# connector_hub.net
KiCad netlist of a schematic drawn in EAGLE
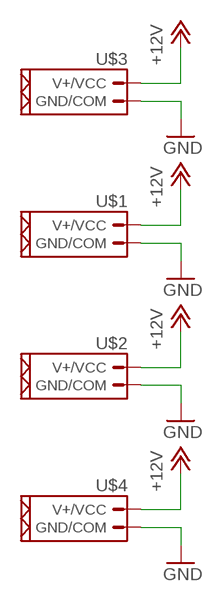
[diagram p0: schematic, sheet 1]

(export (version "E")
  (design (tool "Eeschema 10.0.6"))
  (components
    (comp (ref "U$1")
      (value "CONN_02_PUIXT60")
      (footprint "eagle-import:XT60")
      (libsource (lib "eagle-import") (part "CONN_02_PUIXT60"))
    )
    (comp (ref "U$2")
      (value "CONN_02_PUIXT60")
      (footprint "eagle-import:XT60")
      (libsource (lib "eagle-import") (part "CONN_02_PUIXT60"))
    )
    (comp (ref "U$3")
      (value "CONN_02_PUIXT60")
      (footprint "eagle-import:XT60")
      (libsource (lib "eagle-import") (part "CONN_02_PUIXT60"))
    )
    (comp (ref "U$4")
      (value "CONN_02_PUIXT60")
      (footprint "eagle-import:XT60")
      (libsource (lib "eagle-import") (part "CONN_02_PUIXT60"))
    )
  )
  (nets
    (net (code "1") (name "+12V") (class "Default")
      (node (ref "U$1") (pin "P$1") (pinfunction "V+/VCC_P$1") (pintype "passive"))
      (node (ref "U$2") (pin "P$1") (pinfunction "V+/VCC_P$1") (pintype "passive"))
      (node (ref "U$3") (pin "P$1") (pinfunction "V+/VCC_P$1") (pintype "passive"))
      (node (ref "U$4") (pin "P$1") (pinfunction "V+/VCC_P$1") (pintype "passive"))
    )
    (net (code "2") (name "GND") (class "Default")
      (node (ref "U$1") (pin "P$2") (pinfunction "GND/COM_P$2") (pintype "passive"))
      (node (ref "U$2") (pin "P$2") (pinfunction "GND/COM_P$2") (pintype "passive"))
      (node (ref "U$3") (pin "P$2") (pinfunction "GND/COM_P$2") (pintype "passive"))
      (node (ref "U$4") (pin "P$2") (pinfunction "GND/COM_P$2") (pintype "passive"))
    )
  )
)
